# EEM_Connectors.net
KiCad netlist of a schematic drawn in Altium Designer
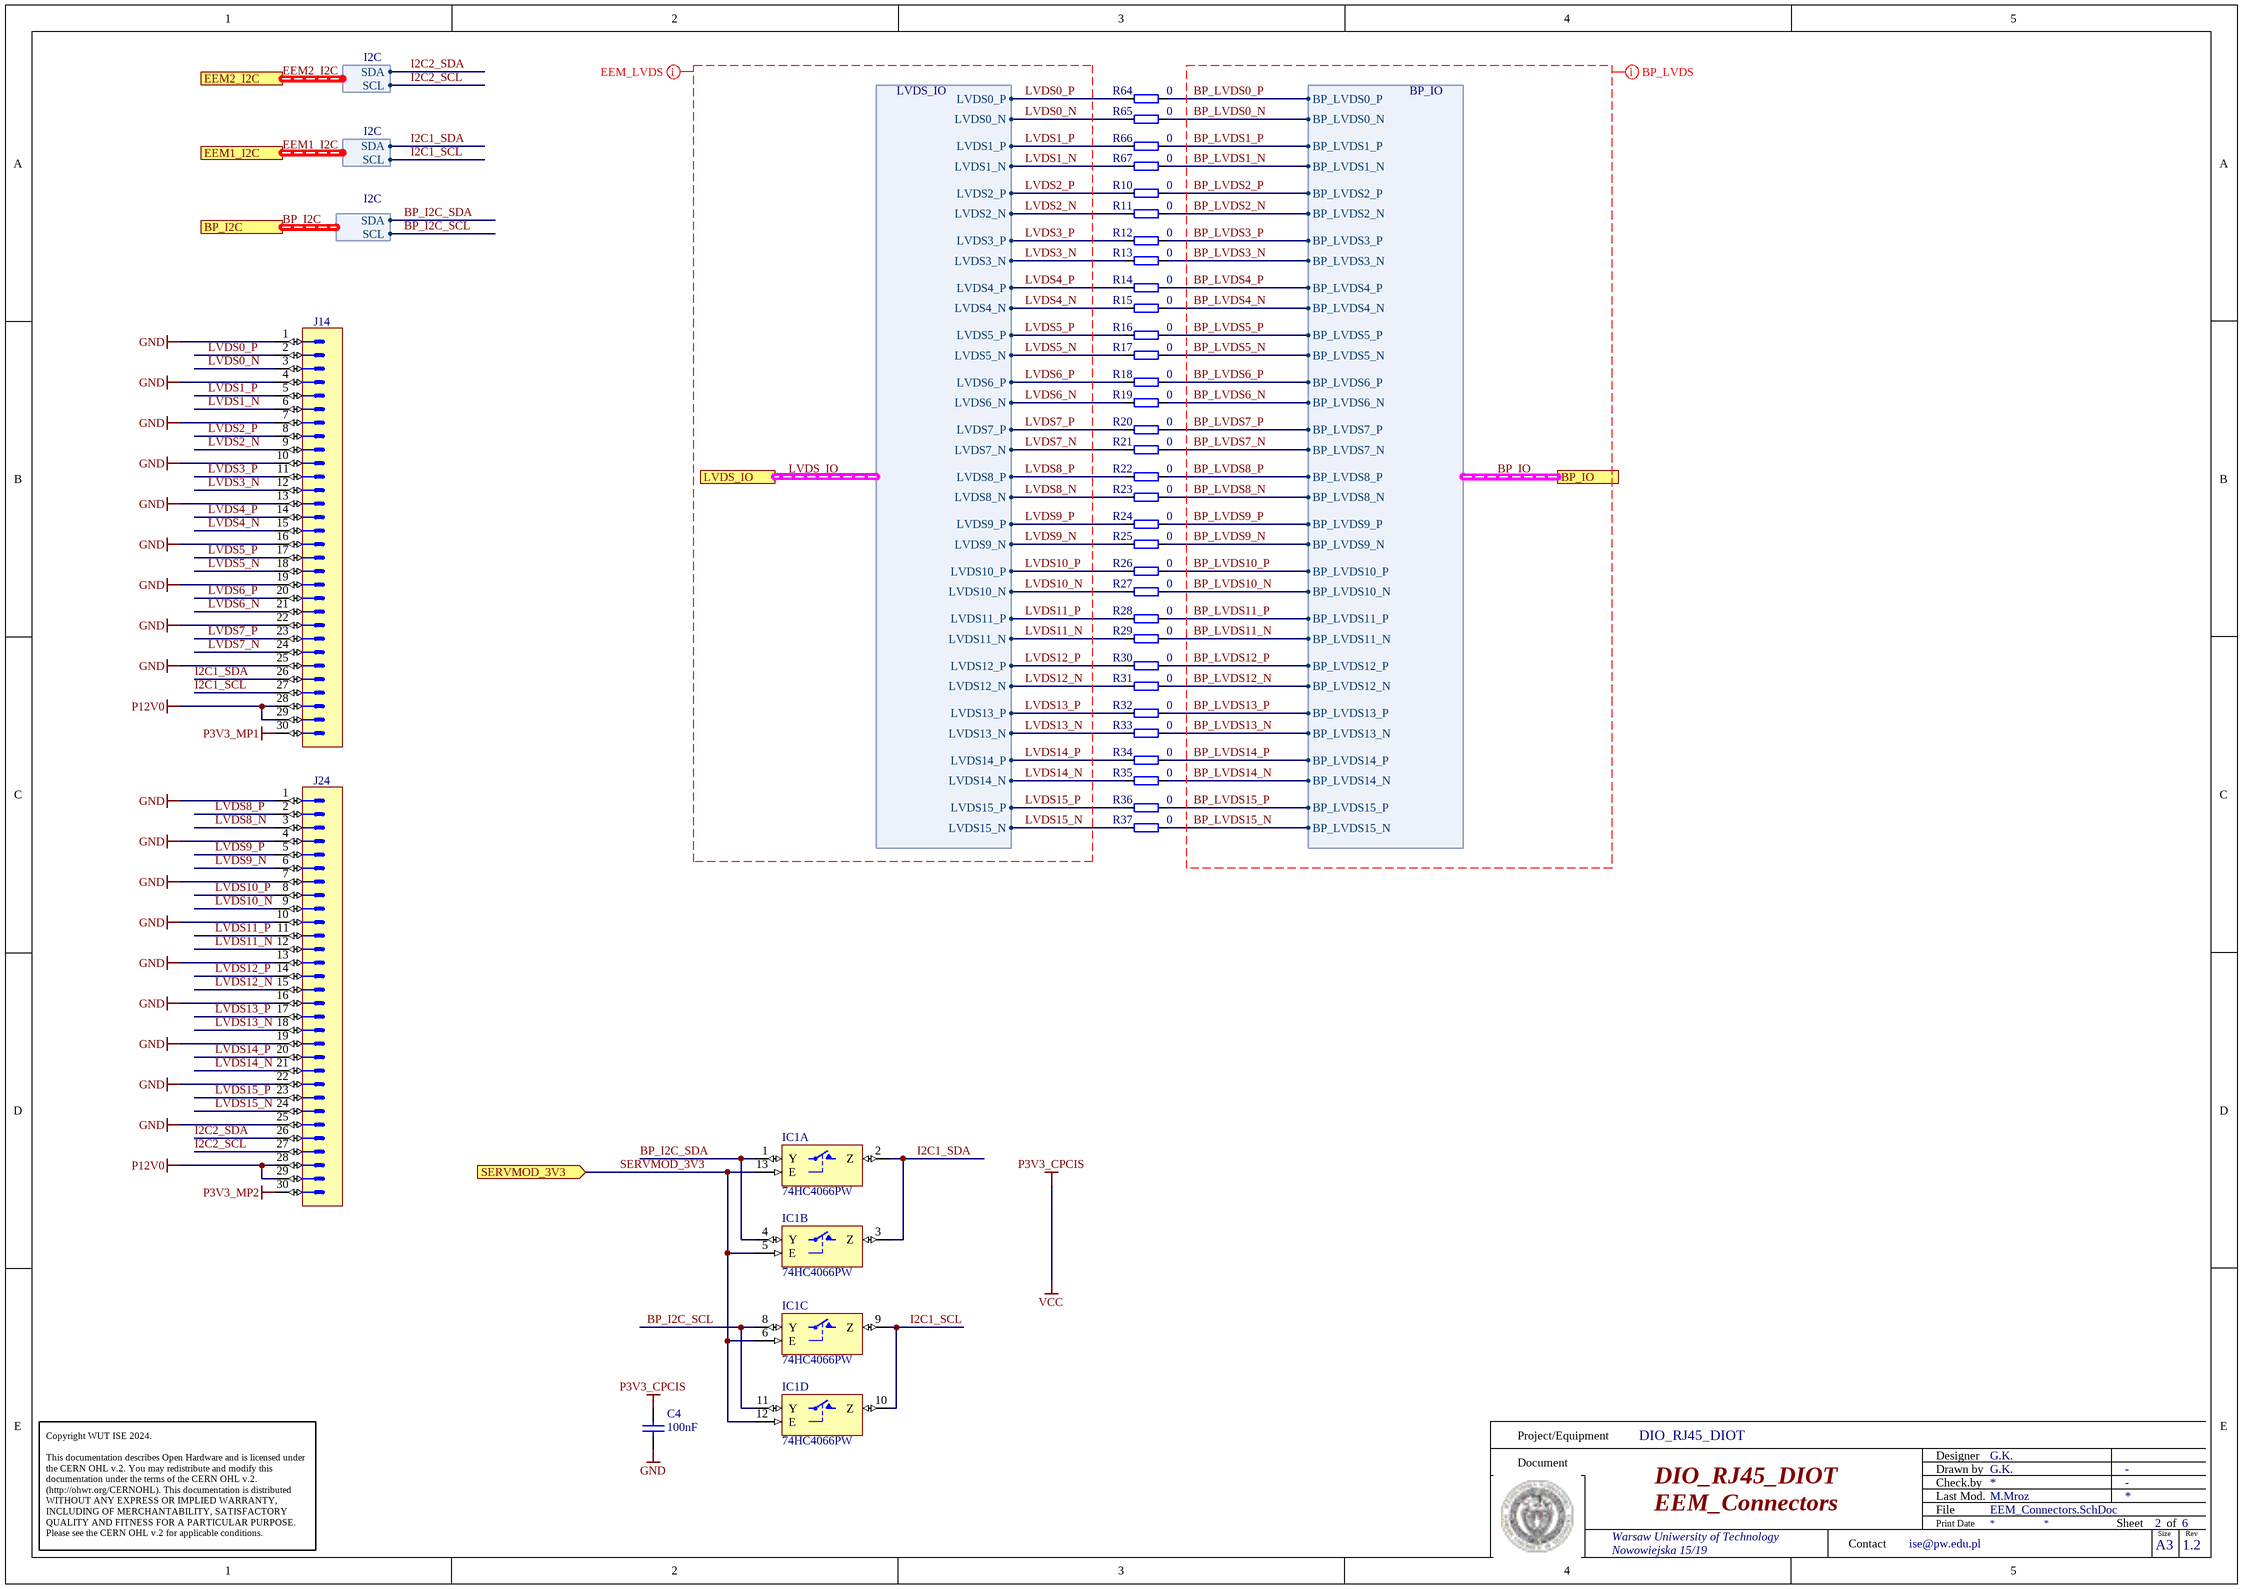
[diagram p0: EEM_Connectors.SchDoc]

(export (version "E")
  (design (tool "Eeschema 10.0.6"))
  (components
    (comp (ref "C4")
      (value "100nF")
      (footprint "CAPC1608X87N")
      (description "Non-polarised capacitor")
      (fields
        (field (name "PART NUMBER") "CC0603_100NF_50V_10%_X7R")
        (field (name "VOLTAGE") "50V")
        (field (name "AUTHOR") "CERN DEM JLC")
      )
      (libsource (lib "Capacitors") (part "Capacitor - non polarized"))
    )
    (comp (ref "IC1")
      (value "74HC4066PW")
      (footprint "SOP65P640X110-14N")
      (fields (field (name "MANUFACTURER") "NXP SEMICONDUCTORS") (field (name "AUTHOR") "CERN DEM JLC"))
      (libsource (lib "ICs And Semiconductors") (part "4066"))
    )
    (comp (ref "J14")
      (value "~")
      (footprint "3M_N2530-6002RB")
      (description "Connector 30 Male")
      (fields
        (field (name "PART NUMBER") "3M_N2530-6002RB")
        (field (name "MANUFACTURER") "3M")
        (field (name "AUTHOR") "CERN DEM JLC")
      )
      (libsource (lib "Connectors") (part "Connector 30 Male"))
    )
    (comp (ref "J24")
      (value "~")
      (footprint "3M_N2530-6002RB")
      (description "Connector 30 Male")
      (fields
        (field (name "PART NUMBER") "3M_N2530-6002RB")
        (field (name "MANUFACTURER") "3M")
        (field (name "AUTHOR") "CERN DEM JLC")
      )
      (libsource (lib "Connectors") (part "Connector 30 Male"))
    )
    (comp (ref "R10")
      (value "0")
      (footprint "RESC1005X35N")
      (description "Resistor")
      (fields
        (field (name "PART NUMBER") "R0402_0R_JUMPER")
        (field (name "MANUFACTURER") "GENERIC")
        (field (name "AUTHOR") "CERN DEM JLC")
      )
      (libsource (lib "Resistors") (part "Resistor"))
    )
    (comp (ref "R11")
      (value "0")
      (footprint "RESC1005X35N")
      (description "Resistor")
      (fields
        (field (name "PART NUMBER") "R0402_0R_JUMPER")
        (field (name "MANUFACTURER") "GENERIC")
        (field (name "AUTHOR") "CERN DEM JLC")
      )
      (libsource (lib "Resistors") (part "Resistor"))
    )
    (comp (ref "R12")
      (value "0")
      (footprint "RESC1005X35N")
      (description "Resistor")
      (fields
        (field (name "PART NUMBER") "R0402_0R_JUMPER")
        (field (name "MANUFACTURER") "GENERIC")
        (field (name "AUTHOR") "CERN DEM JLC")
      )
      (libsource (lib "Resistors") (part "Resistor"))
    )
    (comp (ref "R13")
      (value "0")
      (footprint "RESC1005X35N")
      (description "Resistor")
      (fields
        (field (name "PART NUMBER") "R0402_0R_JUMPER")
        (field (name "MANUFACTURER") "GENERIC")
        (field (name "AUTHOR") "CERN DEM JLC")
      )
      (libsource (lib "Resistors") (part "Resistor"))
    )
    (comp (ref "R14")
      (value "0")
      (footprint "RESC1005X35N")
      (description "Resistor")
      (fields
        (field (name "PART NUMBER") "R0402_0R_JUMPER")
        (field (name "MANUFACTURER") "GENERIC")
        (field (name "AUTHOR") "CERN DEM JLC")
      )
      (libsource (lib "Resistors") (part "Resistor"))
    )
    (comp (ref "R15")
      (value "0")
      (footprint "RESC1005X35N")
      (description "Resistor")
      (fields
        (field (name "PART NUMBER") "R0402_0R_JUMPER")
        (field (name "MANUFACTURER") "GENERIC")
        (field (name "AUTHOR") "CERN DEM JLC")
      )
      (libsource (lib "Resistors") (part "Resistor"))
    )
    (comp (ref "R16")
      (value "0")
      (footprint "RESC1005X35N")
      (description "Resistor")
      (fields
        (field (name "PART NUMBER") "R0402_0R_JUMPER")
        (field (name "MANUFACTURER") "GENERIC")
        (field (name "AUTHOR") "CERN DEM JLC")
      )
      (libsource (lib "Resistors") (part "Resistor"))
    )
    (comp (ref "R17")
      (value "0")
      (footprint "RESC1005X35N")
      (description "Resistor")
      (fields
        (field (name "PART NUMBER") "R0402_0R_JUMPER")
        (field (name "MANUFACTURER") "GENERIC")
        (field (name "AUTHOR") "CERN DEM JLC")
      )
      (libsource (lib "Resistors") (part "Resistor"))
    )
    (comp (ref "R18")
      (value "0")
      (footprint "RESC1005X35N")
      (description "Resistor")
      (fields
        (field (name "PART NUMBER") "R0402_0R_JUMPER")
        (field (name "MANUFACTURER") "GENERIC")
        (field (name "AUTHOR") "CERN DEM JLC")
      )
      (libsource (lib "Resistors") (part "Resistor"))
    )
    (comp (ref "R19")
      (value "0")
      (footprint "RESC1005X35N")
      (description "Resistor")
      (fields
        (field (name "PART NUMBER") "R0402_0R_JUMPER")
        (field (name "MANUFACTURER") "GENERIC")
        (field (name "AUTHOR") "CERN DEM JLC")
      )
      (libsource (lib "Resistors") (part "Resistor"))
    )
    (comp (ref "R20")
      (value "0")
      (footprint "RESC1005X35N")
      (description "Resistor")
      (fields
        (field (name "PART NUMBER") "R0402_0R_JUMPER")
        (field (name "MANUFACTURER") "GENERIC")
        (field (name "AUTHOR") "CERN DEM JLC")
      )
      (libsource (lib "Resistors") (part "Resistor"))
    )
    (comp (ref "R21")
      (value "0")
      (footprint "RESC1005X35N")
      (description "Resistor")
      (fields
        (field (name "PART NUMBER") "R0402_0R_JUMPER")
        (field (name "MANUFACTURER") "GENERIC")
        (field (name "AUTHOR") "CERN DEM JLC")
      )
      (libsource (lib "Resistors") (part "Resistor"))
    )
    (comp (ref "R22")
      (value "0")
      (footprint "RESC1005X35N")
      (description "Resistor")
      (fields
        (field (name "PART NUMBER") "R0402_0R_JUMPER")
        (field (name "MANUFACTURER") "GENERIC")
        (field (name "AUTHOR") "CERN DEM JLC")
      )
      (libsource (lib "Resistors") (part "Resistor"))
    )
    (comp (ref "R23")
      (value "0")
      (footprint "RESC1005X35N")
      (description "Resistor")
      (fields
        (field (name "PART NUMBER") "R0402_0R_JUMPER")
        (field (name "MANUFACTURER") "GENERIC")
        (field (name "AUTHOR") "CERN DEM JLC")
      )
      (libsource (lib "Resistors") (part "Resistor"))
    )
    (comp (ref "R24")
      (value "0")
      (footprint "RESC1005X35N")
      (description "Resistor")
      (fields
        (field (name "PART NUMBER") "R0402_0R_JUMPER")
        (field (name "MANUFACTURER") "GENERIC")
        (field (name "AUTHOR") "CERN DEM JLC")
      )
      (libsource (lib "Resistors") (part "Resistor"))
    )
    (comp (ref "R25")
      (value "0")
      (footprint "RESC1005X35N")
      (description "Resistor")
      (fields
        (field (name "PART NUMBER") "R0402_0R_JUMPER")
        (field (name "MANUFACTURER") "GENERIC")
        (field (name "AUTHOR") "CERN DEM JLC")
      )
      (libsource (lib "Resistors") (part "Resistor"))
    )
    (comp (ref "R26")
      (value "0")
      (footprint "RESC1005X35N")
      (description "Resistor")
      (fields
        (field (name "PART NUMBER") "R0402_0R_JUMPER")
        (field (name "MANUFACTURER") "GENERIC")
        (field (name "AUTHOR") "CERN DEM JLC")
      )
      (libsource (lib "Resistors") (part "Resistor"))
    )
    (comp (ref "R27")
      (value "0")
      (footprint "RESC1005X35N")
      (description "Resistor")
      (fields
        (field (name "PART NUMBER") "R0402_0R_JUMPER")
        (field (name "MANUFACTURER") "GENERIC")
        (field (name "AUTHOR") "CERN DEM JLC")
      )
      (libsource (lib "Resistors") (part "Resistor"))
    )
    (comp (ref "R28")
      (value "0")
      (footprint "RESC1005X35N")
      (description "Resistor")
      (fields
        (field (name "PART NUMBER") "R0402_0R_JUMPER")
        (field (name "MANUFACTURER") "GENERIC")
        (field (name "AUTHOR") "CERN DEM JLC")
      )
      (libsource (lib "Resistors") (part "Resistor"))
    )
    (comp (ref "R29")
      (value "0")
      (footprint "RESC1005X35N")
      (description "Resistor")
      (fields
        (field (name "PART NUMBER") "R0402_0R_JUMPER")
        (field (name "MANUFACTURER") "GENERIC")
        (field (name "AUTHOR") "CERN DEM JLC")
      )
      (libsource (lib "Resistors") (part "Resistor"))
    )
    (comp (ref "R30")
      (value "0")
      (footprint "RESC1005X35N")
      (description "Resistor")
      (fields
        (field (name "PART NUMBER") "R0402_0R_JUMPER")
        (field (name "MANUFACTURER") "GENERIC")
        (field (name "AUTHOR") "CERN DEM JLC")
      )
      (libsource (lib "Resistors") (part "Resistor"))
    )
    (comp (ref "R31")
      (value "0")
      (footprint "RESC1005X35N")
      (description "Resistor")
      (fields
        (field (name "PART NUMBER") "R0402_0R_JUMPER")
        (field (name "MANUFACTURER") "GENERIC")
        (field (name "AUTHOR") "CERN DEM JLC")
      )
      (libsource (lib "Resistors") (part "Resistor"))
    )
    (comp (ref "R32")
      (value "0")
      (footprint "RESC1005X35N")
      (description "Resistor")
      (fields
        (field (name "PART NUMBER") "R0402_0R_JUMPER")
        (field (name "MANUFACTURER") "GENERIC")
        (field (name "AUTHOR") "CERN DEM JLC")
      )
      (libsource (lib "Resistors") (part "Resistor"))
    )
    (comp (ref "R33")
      (value "0")
      (footprint "RESC1005X35N")
      (description "Resistor")
      (fields
        (field (name "PART NUMBER") "R0402_0R_JUMPER")
        (field (name "MANUFACTURER") "GENERIC")
        (field (name "AUTHOR") "CERN DEM JLC")
      )
      (libsource (lib "Resistors") (part "Resistor"))
    )
    (comp (ref "R34")
      (value "0")
      (footprint "RESC1005X35N")
      (description "Resistor")
      (fields
        (field (name "PART NUMBER") "R0402_0R_JUMPER")
        (field (name "MANUFACTURER") "GENERIC")
        (field (name "AUTHOR") "CERN DEM JLC")
      )
      (libsource (lib "Resistors") (part "Resistor"))
    )
    (comp (ref "R35")
      (value "0")
      (footprint "RESC1005X35N")
      (description "Resistor")
      (fields
        (field (name "PART NUMBER") "R0402_0R_JUMPER")
        (field (name "MANUFACTURER") "GENERIC")
        (field (name "AUTHOR") "CERN DEM JLC")
      )
      (libsource (lib "Resistors") (part "Resistor"))
    )
    (comp (ref "R36")
      (value "0")
      (footprint "RESC1005X35N")
      (description "Resistor")
      (fields
        (field (name "PART NUMBER") "R0402_0R_JUMPER")
        (field (name "MANUFACTURER") "GENERIC")
        (field (name "AUTHOR") "CERN DEM JLC")
      )
      (libsource (lib "Resistors") (part "Resistor"))
    )
    (comp (ref "R37")
      (value "0")
      (footprint "RESC1005X35N")
      (description "Resistor")
      (fields
        (field (name "PART NUMBER") "R0402_0R_JUMPER")
        (field (name "MANUFACTURER") "GENERIC")
        (field (name "AUTHOR") "CERN DEM JLC")
      )
      (libsource (lib "Resistors") (part "Resistor"))
    )
    (comp (ref "R64")
      (value "0")
      (footprint "RESC1005X35N")
      (description "Resistor")
      (fields
        (field (name "PART NUMBER") "R0402_0R_JUMPER")
        (field (name "MANUFACTURER") "GENERIC")
        (field (name "AUTHOR") "CERN DEM JLC")
      )
      (libsource (lib "Resistors") (part "Resistor"))
    )
    (comp (ref "R65")
      (value "0")
      (footprint "RESC1005X35N")
      (description "Resistor")
      (fields
        (field (name "PART NUMBER") "R0402_0R_JUMPER")
        (field (name "MANUFACTURER") "GENERIC")
        (field (name "AUTHOR") "CERN DEM JLC")
      )
      (libsource (lib "Resistors") (part "Resistor"))
    )
    (comp (ref "R66")
      (value "0")
      (footprint "RESC1005X35N")
      (description "Resistor")
      (fields
        (field (name "PART NUMBER") "R0402_0R_JUMPER")
        (field (name "MANUFACTURER") "GENERIC")
        (field (name "AUTHOR") "CERN DEM JLC")
      )
      (libsource (lib "Resistors") (part "Resistor"))
    )
    (comp (ref "R67")
      (value "0")
      (footprint "RESC1005X35N")
      (description "Resistor")
      (fields
        (field (name "PART NUMBER") "R0402_0R_JUMPER")
        (field (name "MANUFACTURER") "GENERIC")
        (field (name "AUTHOR") "CERN DEM JLC")
      )
      (libsource (lib "Resistors") (part "Resistor"))
    )
  )
  (nets
    (net (code "6") (name "/BP_I2C_SCL") (class "Default")
      (node (ref "IC1") (pin "11") (pinfunction "Y_11") (pintype "bidirectional"))
      (node (ref "IC1") (pin "8") (pinfunction "Y_8") (pintype "bidirectional"))
    )
    (net (code "7") (name "/BP_I2C_SDA") (class "Default")
      (node (ref "IC1") (pin "1") (pinfunction "Y_1") (pintype "bidirectional"))
      (node (ref "IC1") (pin "4") (pinfunction "Y_4") (pintype "bidirectional"))
    )
    (net (code "10") (name "/BP_LVDS0_N") (class "Default")
      (node (ref "R65") (pin "1") (pinfunction "1_1") (pintype "passive"))
    )
    (net (code "11") (name "/BP_LVDS0_P") (class "Default")
      (node (ref "R64") (pin "1") (pinfunction "1_1") (pintype "passive"))
    )
    (net (code "12") (name "/BP_LVDS1_N") (class "Default")
      (node (ref "R67") (pin "1") (pinfunction "1_1") (pintype "passive"))
    )
    (net (code "13") (name "/BP_LVDS1_P") (class "Default")
      (node (ref "R66") (pin "1") (pinfunction "1_1") (pintype "passive"))
    )
    (net (code "14") (name "/BP_LVDS2_N") (class "Default")
      (node (ref "R11") (pin "1") (pinfunction "1_1") (pintype "passive"))
    )
    (net (code "15") (name "/BP_LVDS2_P") (class "Default")
      (node (ref "R10") (pin "1") (pinfunction "1_1") (pintype "passive"))
    )
    (net (code "16") (name "/BP_LVDS3_N") (class "Default")
      (node (ref "R13") (pin "1") (pinfunction "1_1") (pintype "passive"))
    )
    (net (code "17") (name "/BP_LVDS3_P") (class "Default")
      (node (ref "R12") (pin "1") (pinfunction "1_1") (pintype "passive"))
    )
    (net (code "18") (name "/BP_LVDS4_N") (class "Default")
      (node (ref "R15") (pin "1") (pinfunction "1_1") (pintype "passive"))
    )
    (net (code "19") (name "/BP_LVDS4_P") (class "Default")
      (node (ref "R14") (pin "1") (pinfunction "1_1") (pintype "passive"))
    )
    (net (code "20") (name "/BP_LVDS5_N") (class "Default")
      (node (ref "R17") (pin "1") (pinfunction "1_1") (pintype "passive"))
    )
    (net (code "21") (name "/BP_LVDS5_P") (class "Default")
      (node (ref "R16") (pin "1") (pinfunction "1_1") (pintype "passive"))
    )
    (net (code "22") (name "/BP_LVDS6_N") (class "Default")
      (node (ref "R19") (pin "1") (pinfunction "1_1") (pintype "passive"))
    )
    (net (code "23") (name "/BP_LVDS6_P") (class "Default")
      (node (ref "R18") (pin "1") (pinfunction "1_1") (pintype "passive"))
    )
    (net (code "24") (name "/BP_LVDS7_N") (class "Default")
      (node (ref "R21") (pin "1") (pinfunction "1_1") (pintype "passive"))
    )
    (net (code "25") (name "/BP_LVDS7_P") (class "Default")
      (node (ref "R20") (pin "1") (pinfunction "1_1") (pintype "passive"))
    )
    (net (code "26") (name "/BP_LVDS8_N") (class "Default")
      (node (ref "R23") (pin "1") (pinfunction "1_1") (pintype "passive"))
    )
    (net (code "27") (name "/BP_LVDS8_P") (class "Default")
      (node (ref "R22") (pin "1") (pinfunction "1_1") (pintype "passive"))
    )
    (net (code "28") (name "/BP_LVDS9_N") (class "Default")
      (node (ref "R25") (pin "1") (pinfunction "1_1") (pintype "passive"))
    )
    (net (code "29") (name "/BP_LVDS9_P") (class "Default")
      (node (ref "R24") (pin "1") (pinfunction "1_1") (pintype "passive"))
    )
    (net (code "30") (name "/BP_LVDS10_N") (class "Default")
      (node (ref "R27") (pin "1") (pinfunction "1_1") (pintype "passive"))
    )
    (net (code "31") (name "/BP_LVDS10_P") (class "Default")
      (node (ref "R26") (pin "1") (pinfunction "1_1") (pintype "passive"))
    )
    (net (code "32") (name "/BP_LVDS11_N") (class "Default")
      (node (ref "R29") (pin "1") (pinfunction "1_1") (pintype "passive"))
    )
    (net (code "33") (name "/BP_LVDS11_P") (class "Default")
      (node (ref "R28") (pin "1") (pinfunction "1_1") (pintype "passive"))
    )
    (net (code "34") (name "/BP_LVDS12_N") (class "Default")
      (node (ref "R31") (pin "1") (pinfunction "1_1") (pintype "passive"))
    )
    (net (code "35") (name "/BP_LVDS12_P") (class "Default")
      (node (ref "R30") (pin "1") (pinfunction "1_1") (pintype "passive"))
    )
    (net (code "36") (name "/BP_LVDS13_N") (class "Default")
      (node (ref "R33") (pin "1") (pinfunction "1_1") (pintype "passive"))
    )
    (net (code "37") (name "/BP_LVDS13_P") (class "Default")
      (node (ref "R32") (pin "1") (pinfunction "1_1") (pintype "passive"))
    )
    (net (code "38") (name "/BP_LVDS14_N") (class "Default")
      (node (ref "R35") (pin "1") (pinfunction "1_1") (pintype "passive"))
    )
    (net (code "39") (name "/BP_LVDS14_P") (class "Default")
      (node (ref "R34") (pin "1") (pinfunction "1_1") (pintype "passive"))
    )
    (net (code "40") (name "/BP_LVDS15_N") (class "Default")
      (node (ref "R37") (pin "1") (pinfunction "1_1") (pintype "passive"))
    )
    (net (code "41") (name "/BP_LVDS15_P") (class "Default")
      (node (ref "R36") (pin "1") (pinfunction "1_1") (pintype "passive"))
    )
    (net (code "44") (name "/I2C1_SCL") (class "Default")
      (node (ref "IC1") (pin "10") (pinfunction "Z_10") (pintype "bidirectional"))
      (node (ref "IC1") (pin "9") (pinfunction "Z_9") (pintype "bidirectional"))
      (node (ref "J14") (pin "27") (pinfunction "27_27") (pintype "bidirectional"))
    )
    (net (code "45") (name "/I2C1_SDA") (class "Default")
      (node (ref "IC1") (pin "2") (pinfunction "Z_2") (pintype "bidirectional"))
      (node (ref "IC1") (pin "3") (pinfunction "Z_3") (pintype "bidirectional"))
      (node (ref "J14") (pin "26") (pinfunction "26_26") (pintype "bidirectional"))
    )
    (net (code "46") (name "/I2C2_SCL") (class "Default")
      (node (ref "J24") (pin "27") (pinfunction "27_27") (pintype "bidirectional"))
    )
    (net (code "47") (name "/I2C2_SDA") (class "Default")
      (node (ref "J24") (pin "26") (pinfunction "26_26") (pintype "bidirectional"))
    )
    (net (code "48") (name "/LVDS0_N") (class "Default")
      (node (ref "J14") (pin "3") (pinfunction "3_3") (pintype "bidirectional"))
      (node (ref "R65") (pin "2") (pinfunction "2_2") (pintype "passive"))
    )
    (net (code "49") (name "/LVDS0_P") (class "Default")
      (node (ref "J14") (pin "2") (pinfunction "2_2") (pintype "bidirectional"))
      (node (ref "R64") (pin "2") (pinfunction "2_2") (pintype "passive"))
    )
    (net (code "50") (name "/LVDS1_N") (class "Default")
      (node (ref "J14") (pin "6") (pinfunction "6_6") (pintype "bidirectional"))
      (node (ref "R67") (pin "2") (pinfunction "2_2") (pintype "passive"))
    )
    (net (code "51") (name "/LVDS1_P") (class "Default")
      (node (ref "J14") (pin "5") (pinfunction "5_5") (pintype "bidirectional"))
      (node (ref "R66") (pin "2") (pinfunction "2_2") (pintype "passive"))
    )
    (net (code "52") (name "/LVDS2_N") (class "Default")
      (node (ref "J14") (pin "9") (pinfunction "9_9") (pintype "bidirectional"))
      (node (ref "R11") (pin "2") (pinfunction "2_2") (pintype "passive"))
    )
    (net (code "53") (name "/LVDS2_P") (class "Default")
      (node (ref "J14") (pin "8") (pinfunction "8_8") (pintype "bidirectional"))
      (node (ref "R10") (pin "2") (pinfunction "2_2") (pintype "passive"))
    )
    (net (code "54") (name "/LVDS3_N") (class "Default")
      (node (ref "J14") (pin "12") (pinfunction "12_12") (pintype "bidirectional"))
      (node (ref "R13") (pin "2") (pinfunction "2_2") (pintype "passive"))
    )
    (net (code "55") (name "/LVDS3_P") (class "Default")
      (node (ref "J14") (pin "11") (pinfunction "11_11") (pintype "bidirectional"))
      (node (ref "R12") (pin "2") (pinfunction "2_2") (pintype "passive"))
    )
    (net (code "56") (name "/LVDS4_N") (class "Default")
      (node (ref "J14") (pin "15") (pinfunction "15_15") (pintype "bidirectional"))
      (node (ref "R15") (pin "2") (pinfunction "2_2") (pintype "passive"))
    )
    (net (code "57") (name "/LVDS4_P") (class "Default")
      (node (ref "J14") (pin "14") (pinfunction "14_14") (pintype "bidirectional"))
      (node (ref "R14") (pin "2") (pinfunction "2_2") (pintype "passive"))
    )
    (net (code "58") (name "/LVDS5_N") (class "Default")
      (node (ref "J14") (pin "18") (pinfunction "18_18") (pintype "bidirectional"))
      (node (ref "R17") (pin "2") (pinfunction "2_2") (pintype "passive"))
    )
    (net (code "59") (name "/LVDS5_P") (class "Default")
      (node (ref "J14") (pin "17") (pinfunction "17_17") (pintype "bidirectional"))
      (node (ref "R16") (pin "2") (pinfunction "2_2") (pintype "passive"))
    )
    (net (code "60") (name "/LVDS6_N") (class "Default")
      (node (ref "J14") (pin "21") (pinfunction "21_21") (pintype "bidirectional"))
      (node (ref "R19") (pin "2") (pinfunction "2_2") (pintype "passive"))
    )
    (net (code "61") (name "/LVDS6_P") (class "Default")
      (node (ref "J14") (pin "20") (pinfunction "20_20") (pintype "bidirectional"))
      (node (ref "R18") (pin "2") (pinfunction "2_2") (pintype "passive"))
    )
    (net (code "62") (name "/LVDS7_N") (class "Default")
      (node (ref "J14") (pin "24") (pinfunction "24_24") (pintype "bidirectional"))
      (node (ref "R21") (pin "2") (pinfunction "2_2") (pintype "passive"))
    )
    (net (code "63") (name "/LVDS7_P") (class "Default")
      (node (ref "J14") (pin "23") (pinfunction "23_23") (pintype "bidirectional"))
      (node (ref "R20") (pin "2") (pinfunction "2_2") (pintype "passive"))
    )
    (net (code "64") (name "/LVDS8_N") (class "Default")
      (node (ref "J24") (pin "3") (pinfunction "3_3") (pintype "bidirectional"))
      (node (ref "R23") (pin "2") (pinfunction "2_2") (pintype "passive"))
    )
    (net (code "65") (name "/LVDS8_P") (class "Default")
      (node (ref "J24") (pin "2") (pinfunction "2_2") (pintype "bidirectional"))
      (node (ref "R22") (pin "2") (pinfunction "2_2") (pintype "passive"))
    )
    (net (code "66") (name "/LVDS9_N") (class "Default")
      (node (ref "J24") (pin "6") (pinfunction "6_6") (pintype "bidirectional"))
      (node (ref "R25") (pin "2") (pinfunction "2_2") (pintype "passive"))
    )
    (net (code "67") (name "/LVDS9_P") (class "Default")
      (node (ref "J24") (pin "5") (pinfunction "5_5") (pintype "bidirectional"))
      (node (ref "R24") (pin "2") (pinfunction "2_2") (pintype "passive"))
    )
    (net (code "68") (name "/LVDS10_N") (class "Default")
      (node (ref "J24") (pin "9") (pinfunction "9_9") (pintype "bidirectional"))
      (node (ref "R27") (pin "2") (pinfunction "2_2") (pintype "passive"))
    )
    (net (code "69") (name "/LVDS10_P") (class "Default")
      (node (ref "J24") (pin "8") (pinfunction "8_8") (pintype "bidirectional"))
      (node (ref "R26") (pin "2") (pinfunction "2_2") (pintype "passive"))
    )
    (net (code "70") (name "/LVDS11_N") (class "Default")
      (node (ref "J24") (pin "12") (pinfunction "12_12") (pintype "bidirectional"))
      (node (ref "R29") (pin "2") (pinfunction "2_2") (pintype "passive"))
    )
    (net (code "71") (name "/LVDS11_P") (class "Default")
      (node (ref "J24") (pin "11") (pinfunction "11_11") (pintype "bidirectional"))
      (node (ref "R28") (pin "2") (pinfunction "2_2") (pintype "passive"))
    )
    (net (code "72") (name "/LVDS12_N") (class "Default")
      (node (ref "J24") (pin "15") (pinfunction "15_15") (pintype "bidirectional"))
      (node (ref "R31") (pin "2") (pinfunction "2_2") (pintype "passive"))
    )
    (net (code "73") (name "/LVDS12_P") (class "Default")
      (node (ref "J24") (pin "14") (pinfunction "14_14") (pintype "bidirectional"))
      (node (ref "R30") (pin "2") (pinfunction "2_2") (pintype "passive"))
    )
    (net (code "74") (name "/LVDS13_N") (class "Default")
      (node (ref "J24") (pin "18") (pinfunction "18_18") (pintype "bidirectional"))
      (node (ref "R33") (pin "2") (pinfunction "2_2") (pintype "passive"))
    )
    (net (code "75") (name "/LVDS13_P") (class "Default")
      (node (ref "J24") (pin "17") (pinfunction "17_17") (pintype "bidirectional"))
      (node (ref "R32") (pin "2") (pinfunction "2_2") (pintype "passive"))
    )
    (net (code "76") (name "/LVDS14_N") (class "Default")
      (node (ref "J24") (pin "21") (pinfunction "21_21") (pintype "bidirectional"))
      (node (ref "R35") (pin "2") (pinfunction "2_2") (pintype "passive"))
    )
    (net (code "77") (name "/LVDS14_P") (class "Default")
      (node (ref "J24") (pin "20") (pinfunction "20_20") (pintype "bidirectional"))
      (node (ref "R34") (pin "2") (pinfunction "2_2") (pintype "passive"))
    )
    (net (code "78") (name "/LVDS15_N") (class "Default")
      (node (ref "J24") (pin "24") (pinfunction "24_24") (pintype "bidirectional"))
      (node (ref "R37") (pin "2") (pinfunction "2_2") (pintype "passive"))
    )
    (net (code "79") (name "/LVDS15_P") (class "Default")
      (node (ref "J24") (pin "23") (pinfunction "23_23") (pintype "bidirectional"))
      (node (ref "R36") (pin "2") (pinfunction "2_2") (pintype "passive"))
    )
    (net (code "81") (name "/SERVMOD_3V3") (class "Default")
      (node (ref "IC1") (pin "12") (pinfunction "E_12") (pintype "input"))
      (node (ref "IC1") (pin "13") (pinfunction "E_13") (pintype "input"))
      (node (ref "IC1") (pin "5") (pinfunction "E_5") (pintype "input"))
      (node (ref "IC1") (pin "6") (pinfunction "E_6") (pintype "input"))
    )
    (net (code "82") (name "GND") (class "Default")
      (node (ref "C4") (pin "1") (pinfunction "1_1") (pintype "passive"))
      (node (ref "IC1") (pin "7") (pinfunction "GND_7") (pintype "power_in"))
      (node (ref "J14") (pin "1") (pinfunction "1_1") (pintype "bidirectional"))
      (node (ref "J14") (pin "10") (pinfunction "10_10") (pintype "bidirectional"))
      (node (ref "J14") (pin "13") (pinfunction "13_13") (pintype "bidirectional"))
      (node (ref "J14") (pin "16") (pinfunction "16_16") (pintype "bidirectional"))
      (node (ref "J14") (pin "19") (pinfunction "19_19") (pintype "bidirectional"))
      (node (ref "J14") (pin "22") (pinfunction "22_22") (pintype "bidirectional"))
      (node (ref "J14") (pin "25") (pinfunction "25_25") (pintype "bidirectional"))
      (node (ref "J14") (pin "4") (pinfunction "4_4") (pintype "bidirectional"))
      (node (ref "J14") (pin "7") (pinfunction "7_7") (pintype "bidirectional"))
      (node (ref "J24") (pin "1") (pinfunction "1_1") (pintype "bidirectional"))
      (node (ref "J24") (pin "10") (pinfunction "10_10") (pintype "bidirectional"))
      (node (ref "J24") (pin "13") (pinfunction "13_13") (pintype "bidirectional"))
      (node (ref "J24") (pin "16") (pinfunction "16_16") (pintype "bidirectional"))
      (node (ref "J24") (pin "19") (pinfunction "19_19") (pintype "bidirectional"))
      (node (ref "J24") (pin "22") (pinfunction "22_22") (pintype "bidirectional"))
      (node (ref "J24") (pin "25") (pinfunction "25_25") (pintype "bidirectional"))
      (node (ref "J24") (pin "4") (pinfunction "4_4") (pintype "bidirectional"))
      (node (ref "J24") (pin "7") (pinfunction "7_7") (pintype "bidirectional"))
    )
    (net (code "83") (name "P3V3_CPCIS") (class "Default")
      (node (ref "C4") (pin "2") (pinfunction "2_2") (pintype "passive"))
      (node (ref "IC1") (pin "14") (pinfunction "VCC_14") (pintype "power_in"))
    )
    (net (code "84") (name "P3V3_MP1") (class "Default")
      (node (ref "J14") (pin "30") (pinfunction "30_30") (pintype "bidirectional"))
    )
    (net (code "85") (name "P3V3_MP2") (class "Default")
      (node (ref "J24") (pin "30") (pinfunction "30_30") (pintype "bidirectional"))
    )
    (net (code "86") (name "P12V0") (class "Default")
      (node (ref "J14") (pin "28") (pinfunction "28_28") (pintype "bidirectional"))
      (node (ref "J14") (pin "29") (pinfunction "29_29") (pintype "bidirectional"))
      (node (ref "J24") (pin "28") (pinfunction "28_28") (pintype "bidirectional"))
      (node (ref "J24") (pin "29") (pinfunction "29_29") (pintype "bidirectional"))
    )
  )
)
